# SCH12_AFE.net
KiCad netlist of a schematic drawn in Altium Designer
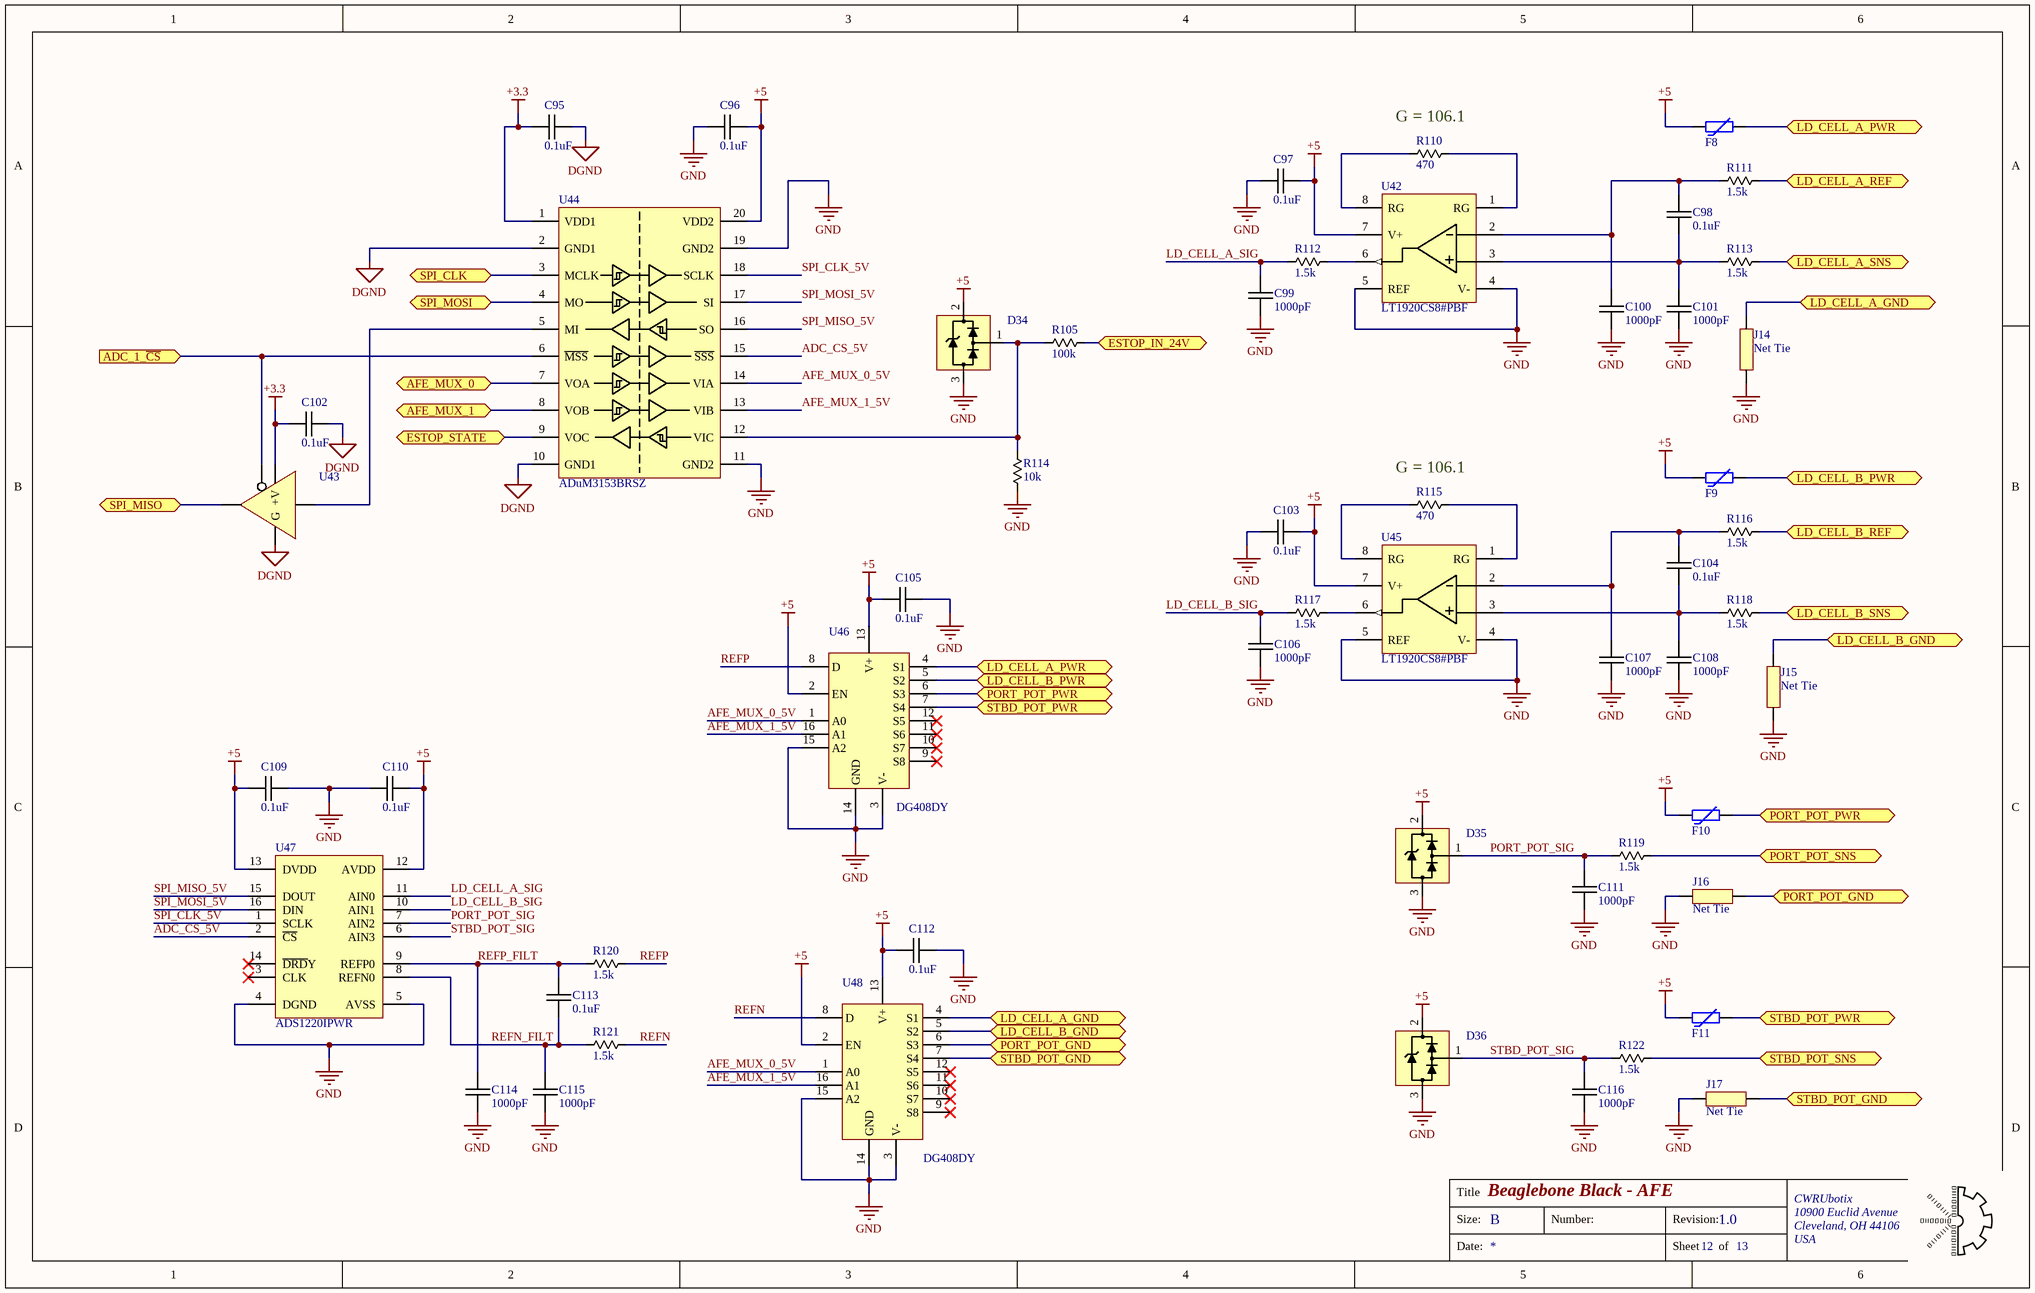
[diagram p0: SCH12_AFE.SchDoc]

(export (version "E")
  (design (tool "Eeschema 10.0.6"))
  (components
    (comp (ref "C95")
      (value "0.1uF")
      (footprint "chip_0603")
      (description "CAP, 0.1uF, ±10%, 16V, X7R, 0603")
      (fields (field (name "PART NUMBER") "CAP-00542") (field (name "TOLERANCE") "±10%"))
      (libsource (lib "Capacitors$") (part "CAP-00542"))
    )
    (comp (ref "C96")
      (value "0.1uF")
      (footprint "chip_0603")
      (description "CAP, 0.1uF, ±10%, 16V, X7R, 0603")
      (fields (field (name "PART NUMBER") "CAP-00542") (field (name "TOLERANCE") "±10%"))
      (libsource (lib "Capacitors$") (part "CAP-00542"))
    )
    (comp (ref "C97")
      (value "0.1uF")
      (footprint "chip_0603")
      (description "CAP, 0.1uF, ±10%, 16V, X7R, 0603")
      (fields (field (name "PART NUMBER") "CAP-00542") (field (name "TOLERANCE") "±10%"))
      (libsource (lib "Capacitors$") (part "CAP-00542"))
    )
    (comp (ref "C98")
      (value "0.1uF")
      (footprint "chip_0603")
      (description "CAP, 0.1uF, ±10%, 16V, X7R, 0603")
      (fields (field (name "PART NUMBER") "CAP-00542") (field (name "TOLERANCE") "±10%"))
      (libsource (lib "Capacitors$") (part "CAP-00542"))
    )
    (comp (ref "C99")
      (value "1000pF")
      (footprint "chip_0603")
      (description "CAP, 1000pF, ±1%, 50V, C0G, 0603")
      (fields (field (name "PART NUMBER") "CAP-00457") (field (name "TOLERANCE") "±1%"))
      (libsource (lib "Capacitors$") (part "CAP-00457"))
    )
    (comp (ref "C100")
      (value "1000pF")
      (footprint "chip_0603")
      (description "CAP, 1000pF, ±1%, 50V, C0G, 0603")
      (fields (field (name "PART NUMBER") "CAP-00457") (field (name "TOLERANCE") "±1%"))
      (libsource (lib "Capacitors$") (part "CAP-00457"))
    )
    (comp (ref "C101")
      (value "1000pF")
      (footprint "chip_0603")
      (description "CAP, 1000pF, ±1%, 50V, C0G, 0603")
      (fields (field (name "PART NUMBER") "CAP-00457") (field (name "TOLERANCE") "±1%"))
      (libsource (lib "Capacitors$") (part "CAP-00457"))
    )
    (comp (ref "C102")
      (value "0.1uF")
      (footprint "chip_0603")
      (description "CAP, 0.1uF, ±10%, 16V, X7R, 0603")
      (fields (field (name "PART NUMBER") "CAP-00542") (field (name "TOLERANCE") "±10%"))
      (libsource (lib "Capacitors$") (part "CAP-00542"))
    )
    (comp (ref "C103")
      (value "0.1uF")
      (footprint "chip_0603")
      (description "CAP, 0.1uF, ±10%, 16V, X7R, 0603")
      (fields (field (name "PART NUMBER") "CAP-00542") (field (name "TOLERANCE") "±10%"))
      (libsource (lib "Capacitors$") (part "CAP-00542"))
    )
    (comp (ref "C104")
      (value "0.1uF")
      (footprint "chip_0603")
      (description "CAP, 0.1uF, ±10%, 16V, X7R, 0603")
      (fields (field (name "PART NUMBER") "CAP-00542") (field (name "TOLERANCE") "±10%"))
      (libsource (lib "Capacitors$") (part "CAP-00542"))
    )
    (comp (ref "C105")
      (value "0.1uF")
      (footprint "chip_0603")
      (description "CAP, 0.1uF, ±10%, 16V, X7R, 0603")
      (fields (field (name "PART NUMBER") "CAP-00542") (field (name "TOLERANCE") "±10%"))
      (libsource (lib "Capacitors$") (part "CAP-00542"))
    )
    (comp (ref "C106")
      (value "1000pF")
      (footprint "chip_0603")
      (description "CAP, 1000pF, ±1%, 50V, C0G, 0603")
      (fields (field (name "PART NUMBER") "CAP-00457") (field (name "TOLERANCE") "±1%"))
      (libsource (lib "Capacitors$") (part "CAP-00457"))
    )
    (comp (ref "C107")
      (value "1000pF")
      (footprint "chip_0603")
      (description "CAP, 1000pF, ±1%, 50V, C0G, 0603")
      (fields (field (name "PART NUMBER") "CAP-00457") (field (name "TOLERANCE") "±1%"))
      (libsource (lib "Capacitors$") (part "CAP-00457"))
    )
    (comp (ref "C108")
      (value "1000pF")
      (footprint "chip_0603")
      (description "CAP, 1000pF, ±1%, 50V, C0G, 0603")
      (fields (field (name "PART NUMBER") "CAP-00457") (field (name "TOLERANCE") "±1%"))
      (libsource (lib "Capacitors$") (part "CAP-00457"))
    )
    (comp (ref "C109")
      (value "0.1uF")
      (footprint "chip_0603")
      (description "CAP, 0.1uF, ±10%, 16V, X7R, 0603")
      (fields (field (name "PART NUMBER") "CAP-00542") (field (name "TOLERANCE") "±10%"))
      (libsource (lib "Capacitors$") (part "CAP-00542"))
    )
    (comp (ref "C110")
      (value "0.1uF")
      (footprint "chip_0603")
      (description "CAP, 0.1uF, ±10%, 16V, X7R, 0603")
      (fields (field (name "PART NUMBER") "CAP-00542") (field (name "TOLERANCE") "±10%"))
      (libsource (lib "Capacitors$") (part "CAP-00542"))
    )
    (comp (ref "C111")
      (value "1000pF")
      (footprint "chip_0603")
      (description "CAP, 1000pF, ±1%, 50V, C0G, 0603")
      (fields (field (name "PART NUMBER") "CAP-00457") (field (name "TOLERANCE") "±1%"))
      (libsource (lib "Capacitors$") (part "CAP-00457"))
    )
    (comp (ref "C112")
      (value "0.1uF")
      (footprint "chip_0603")
      (description "CAP, 0.1uF, ±10%, 16V, X7R, 0603")
      (fields (field (name "PART NUMBER") "CAP-00542") (field (name "TOLERANCE") "±10%"))
      (libsource (lib "Capacitors$") (part "CAP-00542"))
    )
    (comp (ref "C113")
      (value "0.1uF")
      (footprint "chip_0603")
      (description "CAP, 0.1uF, ±10%, 16V, X7R, 0603")
      (fields (field (name "PART NUMBER") "CAP-00542") (field (name "TOLERANCE") "±10%"))
      (libsource (lib "Capacitors$") (part "CAP-00542"))
    )
    (comp (ref "C114")
      (value "1000pF")
      (footprint "chip_0603")
      (description "CAP, 1000pF, ±1%, 50V, C0G, 0603")
      (fields (field (name "PART NUMBER") "CAP-00457") (field (name "TOLERANCE") "±1%"))
      (libsource (lib "Capacitors$") (part "CAP-00457"))
    )
    (comp (ref "C115")
      (value "1000pF")
      (footprint "chip_0603")
      (description "CAP, 1000pF, ±1%, 50V, C0G, 0603")
      (fields (field (name "PART NUMBER") "CAP-00457") (field (name "TOLERANCE") "±1%"))
      (libsource (lib "Capacitors$") (part "CAP-00457"))
    )
    (comp (ref "C116")
      (value "1000pF")
      (footprint "chip_0603")
      (description "CAP, 1000pF, ±1%, 50V, C0G, 0603")
      (fields (field (name "PART NUMBER") "CAP-00457") (field (name "TOLERANCE") "±1%"))
      (libsource (lib "Capacitors$") (part "CAP-00457"))
    )
    (comp (ref "D34")
      (value "DLPT05")
      (footprint "sot-23-3")
      (description "TVS, Steering (Rail-Rail), 9.8V Clamping, 17A Peak Pulse, SOT-23")
      (fields (field (name "PART NUMBER") "DIO-00057") (field (name "MANUFACTURER") "Diodes Incorporated"))
      (libsource (lib "Diodes$") (part "DIO-00057"))
    )
    (comp (ref "D35")
      (value "DLPT05")
      (footprint "sot-23-3")
      (description "TVS, Steering (Rail-Rail), 9.8V Clamping, 17A Peak Pulse, SOT-23")
      (fields (field (name "PART NUMBER") "DIO-00057") (field (name "MANUFACTURER") "Diodes Incorporated"))
      (libsource (lib "Diodes$") (part "DIO-00057"))
    )
    (comp (ref "D36")
      (value "DLPT05")
      (footprint "sot-23-3")
      (description "TVS, Steering (Rail-Rail), 9.8V Clamping, 17A Peak Pulse, SOT-23")
      (fields (field (name "PART NUMBER") "DIO-00057") (field (name "MANUFACTURER") "Diodes Incorporated"))
      (libsource (lib "Diodes$") (part "DIO-00057"))
    )
    (comp (ref "F8")
      (value "PTC_0")
      (footprint "chip_1206")
      (description "PTC Resettable fuse, 6V, 500mA, 1206")
      (fields (field (name "PART NUMBER") "MISC-00008") (field (name "MANUFACTURER") "Eaton"))
      (libsource (lib "Misc$") (part "MISC-00008"))
    )
    (comp (ref "F9")
      (value "PTC_0")
      (footprint "chip_1206")
      (description "PTC Resettable fuse, 6V, 500mA, 1206")
      (fields (field (name "PART NUMBER") "MISC-00008") (field (name "MANUFACTURER") "Eaton"))
      (libsource (lib "Misc$") (part "MISC-00008"))
    )
    (comp (ref "F10")
      (value "PTC_0")
      (footprint "chip_1206")
      (description "PTC Resettable fuse, 6V, 500mA, 1206")
      (fields (field (name "PART NUMBER") "MISC-00008") (field (name "MANUFACTURER") "Eaton"))
      (libsource (lib "Misc$") (part "MISC-00008"))
    )
    (comp (ref "F11")
      (value "PTC_0")
      (footprint "chip_1206")
      (description "PTC Resettable fuse, 6V, 500mA, 1206")
      (fields (field (name "PART NUMBER") "MISC-00008") (field (name "MANUFACTURER") "Eaton"))
      (libsource (lib "Misc$") (part "MISC-00008"))
    )
    (comp (ref "J14")
      (value "Net Tie")
      (footprint "net_tie_0")
      (fields (field (name "PART NUMBER") "MISC-00039"))
      (libsource (lib "") (part "MISC-00039_1"))
    )
    (comp (ref "J15")
      (value "Net Tie")
      (footprint "net_tie_0")
      (fields (field (name "PART NUMBER") "MISC-00039"))
      (libsource (lib "") (part "MISC-00039_1"))
    )
    (comp (ref "J16")
      (value "Net Tie")
      (footprint "net_tie_0")
      (fields (field (name "PART NUMBER") "MISC-00039"))
      (libsource (lib "Misc$") (part "MISC-00039"))
    )
    (comp (ref "J17")
      (value "Net Tie")
      (footprint "net_tie_0")
      (fields (field (name "PART NUMBER") "MISC-00039"))
      (libsource (lib "Misc$") (part "MISC-00039"))
    )
    (comp (ref "R105")
      (value "100k")
      (footprint "chip_0603")
      (description "RES SMD 100K OHM 1% 1/4W 0603")
      (fields (field (name "PART NUMBER") "RES-00301") (field (name "TOLERANCE") "1%"))
      (libsource (lib "Resistors$") (part "RES-00301"))
    )
    (comp (ref "R110")
      (value "470")
      (footprint "chip_0805")
      (description "RES SMD 470 OHM 1% 1/8W 0805")
      (fields (field (name "PART NUMBER") "RES-00237") (field (name "TOLERANCE") "1%"))
      (libsource (lib "Resistors$") (part "RES-00237"))
    )
    (comp (ref "R111")
      (value "1.5k")
      (footprint "chip_0603")
      (description "RES SMD 1.5K OHM 1% 1/4W 0603")
      (fields (field (name "PART NUMBER") "RES-00284") (field (name "TOLERANCE") "1%"))
      (libsource (lib "Resistors$") (part "RES-00284"))
    )
    (comp (ref "R112")
      (value "1.5k")
      (footprint "chip_0603")
      (description "RES SMD 1.5K OHM 1% 1/4W 0603")
      (fields (field (name "PART NUMBER") "RES-00284") (field (name "TOLERANCE") "1%"))
      (libsource (lib "Resistors$") (part "RES-00284"))
    )
    (comp (ref "R113")
      (value "1.5k")
      (footprint "chip_0603")
      (description "RES SMD 1.5K OHM 1% 1/4W 0603")
      (fields (field (name "PART NUMBER") "RES-00284") (field (name "TOLERANCE") "1%"))
      (libsource (lib "Resistors$") (part "RES-00284"))
    )
    (comp (ref "R114")
      (value "10k")
      (footprint "chip_0603")
      (description "RES SMD 10K OHM 1% 1/4W 0603")
      (fields (field (name "PART NUMBER") "RES-00306") (field (name "TOLERANCE") "1%"))
      (libsource (lib "Resistors$") (part "RES-00306"))
    )
    (comp (ref "R115")
      (value "470")
      (footprint "chip_0805")
      (description "RES SMD 470 OHM 1% 1/8W 0805")
      (fields (field (name "PART NUMBER") "RES-00237") (field (name "TOLERANCE") "1%"))
      (libsource (lib "Resistors$") (part "RES-00237"))
    )
    (comp (ref "R116")
      (value "1.5k")
      (footprint "chip_0603")
      (description "RES SMD 1.5K OHM 1% 1/4W 0603")
      (fields (field (name "PART NUMBER") "RES-00284") (field (name "TOLERANCE") "1%"))
      (libsource (lib "Resistors$") (part "RES-00284"))
    )
    (comp (ref "R117")
      (value "1.5k")
      (footprint "chip_0603")
      (description "RES SMD 1.5K OHM 1% 1/4W 0603")
      (fields (field (name "PART NUMBER") "RES-00284") (field (name "TOLERANCE") "1%"))
      (libsource (lib "Resistors$") (part "RES-00284"))
    )
    (comp (ref "R118")
      (value "1.5k")
      (footprint "chip_0603")
      (description "RES SMD 1.5K OHM 1% 1/4W 0603")
      (fields (field (name "PART NUMBER") "RES-00284") (field (name "TOLERANCE") "1%"))
      (libsource (lib "Resistors$") (part "RES-00284"))
    )
    (comp (ref "R119")
      (value "1.5k")
      (footprint "chip_0603")
      (description "RES SMD 1.5K OHM 1% 1/4W 0603")
      (fields (field (name "PART NUMBER") "RES-00284") (field (name "TOLERANCE") "1%"))
      (libsource (lib "Resistors$") (part "RES-00284"))
    )
    (comp (ref "R120")
      (value "1.5k")
      (footprint "chip_0603")
      (description "RES SMD 1.5K OHM 1% 1/4W 0603")
      (fields (field (name "PART NUMBER") "RES-00284") (field (name "TOLERANCE") "1%"))
      (libsource (lib "Resistors$") (part "RES-00284"))
    )
    (comp (ref "R121")
      (value "1.5k")
      (footprint "chip_0603")
      (description "RES SMD 1.5K OHM 1% 1/4W 0603")
      (fields (field (name "PART NUMBER") "RES-00284") (field (name "TOLERANCE") "1%"))
      (libsource (lib "Resistors$") (part "RES-00284"))
    )
    (comp (ref "R122")
      (value "1.5k")
      (footprint "chip_0603")
      (description "RES SMD 1.5K OHM 1% 1/4W 0603")
      (fields (field (name "PART NUMBER") "RES-00284") (field (name "TOLERANCE") "1%"))
      (libsource (lib "Resistors$") (part "RES-00284"))
    )
    (comp (ref "U42")
      (value "LT1920CS8#PBF")
      (footprint "SO-8_1")
      (description "IC, Instrumentation Amp, Single, 4.6 ~ 36V supply, SOIC-8")
      (fields (field (name "PART NUMBER") "ANLG-00071") (field (name "MANUFACTURER") "Linear Technology"))
      (libsource (lib "Analog$") (part "ANLG-00071"))
    )
    (comp (ref "U43")
      (value "SN74AHCT1G125")
      (footprint "sot-23-5")
      (description "Tri-State Buffer, Single, 2-5.5V, SOT-23-5, SN74AHC1G125")
      (fields (field (name "PART NUMBER") "LOGIC-00027") (field (name "MANUFACTURER") "TI"))
      (libsource (lib "Logic$") (part "LOGIC-00027"))
    )
    (comp (ref "U44")
      (value "ADuM3153BRSZ")
      (footprint "tssop-20_1")
      (description "Digital Isolator, SPI-bus optomized, ADuM3151")
      (fields (field (name "PART NUMBER") "IFACE-00029") (field (name "MANUFACTURER") "Analog Devices"))
      (libsource (lib "Interfaces$") (part "IFACE-00029"))
    )
    (comp (ref "U45")
      (value "LT1920CS8#PBF")
      (footprint "SO-8_1")
      (description "IC, Instrumentation Amp, Single, 4.6 ~ 36V supply, SOIC-8")
      (fields (field (name "PART NUMBER") "ANLG-00071") (field (name "MANUFACTURER") "Linear Technology"))
      (libsource (lib "Analog$") (part "ANLG-00071"))
    )
    (comp (ref "U46")
      (value "DG408DY")
      (footprint "SO-16_1")
      (description "Analog Mux, 8:1, 5 ~ 36V, SOIC-16")
      (fields (field (name "PART NUMBER") "ANLG-00072") (field (name "MANUFACTURER") "Vishay"))
      (libsource (lib "Analog$") (part "ANLG-00072"))
    )
    (comp (ref "U47")
      (value "ADS1220IPWR")
      (footprint "TSSOP-16_0_1")
      (description "IC, ADC 24-bit 4-Channel MUX-PGA, Sigma-Delta, 2k SPS, 16-TSSOP")
      (fields (field (name "PART NUMBER") "ANLG-00073") (field (name "MANUFACTURER") "TI"))
      (libsource (lib "Analog$") (part "ANLG-00073"))
    )
    (comp (ref "U48")
      (value "DG408DY")
      (footprint "SO-16_1")
      (description "Analog Mux, 8:1, 5 ~ 36V, SOIC-16")
      (fields (field (name "PART NUMBER") "ANLG-00072") (field (name "MANUFACTURER") "Vishay"))
      (libsource (lib "Analog$") (part "ANLG-00072"))
    )
  )
  (nets
    (net (code "1") (name "+3.3") (class "Default")
      (node (ref "C102") (pin "2") (pinfunction "2_2") (pintype "passive"))
      (node (ref "C95") (pin "2") (pinfunction "2_2") (pintype "passive"))
      (node (ref "U43") (pin "5") (pinfunction "+V_5") (pintype "passive"))
      (node (ref "U44") (pin "1") (pinfunction "VDD1_1") (pintype "passive"))
    )
    (net (code "2") (name "+5") (class "Default")
      (node (ref "C103") (pin "1") (pinfunction "1_1") (pintype "passive"))
      (node (ref "C105") (pin "2") (pinfunction "2_2") (pintype "passive"))
      (node (ref "C109") (pin "2") (pinfunction "2_2") (pintype "passive"))
      (node (ref "C110") (pin "1") (pinfunction "1_1") (pintype "passive"))
      (node (ref "C112") (pin "2") (pinfunction "2_2") (pintype "passive"))
      (node (ref "C96") (pin "1") (pinfunction "1_1") (pintype "passive"))
      (node (ref "C97") (pin "1") (pinfunction "1_1") (pintype "passive"))
      (node (ref "D34") (pin "2") (pinfunction "VCC_2") (pintype "passive"))
      (node (ref "D35") (pin "2") (pinfunction "VCC_2") (pintype "passive"))
      (node (ref "D36") (pin "2") (pinfunction "VCC_2") (pintype "passive"))
      (node (ref "F10") (pin "1") (pinfunction "1_1") (pintype "passive"))
      (node (ref "F11") (pin "1") (pinfunction "1_1") (pintype "passive"))
      (node (ref "F8") (pin "1") (pinfunction "1_1") (pintype "passive"))
      (node (ref "F9") (pin "1") (pinfunction "1_1") (pintype "passive"))
      (node (ref "U42") (pin "7") (pinfunction "V+_7") (pintype "power_in"))
      (node (ref "U44") (pin "20") (pinfunction "VDD2_20") (pintype "passive"))
      (node (ref "U45") (pin "7") (pinfunction "V+_7") (pintype "power_in"))
      (node (ref "U46") (pin "13") (pinfunction "V+_13") (pintype "passive"))
      (node (ref "U46") (pin "2") (pinfunction "EN_2") (pintype "passive"))
      (node (ref "U47") (pin "12") (pinfunction "AVDD_12") (pintype "passive"))
      (node (ref "U47") (pin "13") (pinfunction "DVDD_13") (pintype "passive"))
      (node (ref "U48") (pin "13") (pinfunction "V+_13") (pintype "passive"))
      (node (ref "U48") (pin "2") (pinfunction "EN_2") (pintype "passive"))
    )
    (net (code "3") (name "/ADC_1_~{CS}") (class "Default")
      (node (ref "U43") (pin "1") (pinfunction "~{OE}_1") (pintype "passive"))
      (node (ref "U44") (pin "6") (pinfunction "~{MSS}_6") (pintype "passive"))
    )
    (net (code "4") (name "/ADC_CS_5V") (class "Default")
      (node (ref "U44") (pin "15") (pinfunction "~{SSS}_15") (pintype "passive"))
      (node (ref "U47") (pin "2") (pinfunction "~{CS}_2") (pintype "passive"))
    )
    (net (code "5") (name "/AFE_MUX_0") (class "Default")
      (node (ref "U44") (pin "7") (pinfunction "VOA_7") (pintype "passive"))
    )
    (net (code "6") (name "/AFE_MUX_0_5V") (class "Default")
      (node (ref "U44") (pin "14") (pinfunction "VIA_14") (pintype "passive"))
      (node (ref "U46") (pin "1") (pinfunction "A0_1") (pintype "passive"))
      (node (ref "U48") (pin "1") (pinfunction "A0_1") (pintype "passive"))
    )
    (net (code "7") (name "/AFE_MUX_1") (class "Default")
      (node (ref "U44") (pin "8") (pinfunction "VOB_8") (pintype "passive"))
    )
    (net (code "8") (name "/AFE_MUX_1_5V") (class "Default")
      (node (ref "U44") (pin "13") (pinfunction "VIB_13") (pintype "passive"))
      (node (ref "U46") (pin "16") (pinfunction "A1_16") (pintype "passive"))
      (node (ref "U48") (pin "16") (pinfunction "A1_16") (pintype "passive"))
    )
    (net (code "9") (name "/ESTOP_IN_24V") (class "Default")
      (node (ref "R105") (pin "2") (pinfunction "2_2") (pintype "passive"))
    )
    (net (code "10") (name "/ESTOP_STATE") (class "Default")
      (node (ref "U44") (pin "9") (pinfunction "VOC_9") (pintype "passive"))
    )
    (net (code "11") (name "/LD_CELL_A_GND") (class "Default")
      (node (ref "J14") (pin "2") (pinfunction "NET2_2") (pintype "power_in"))
      (node (ref "U48") (pin "4") (pinfunction "S1_4") (pintype "passive"))
    )
    (net (code "12") (name "/LD_CELL_A_PWR") (class "Default")
      (node (ref "F8") (pin "2") (pinfunction "2_2") (pintype "passive"))
      (node (ref "U46") (pin "4") (pinfunction "S1_4") (pintype "passive"))
    )
    (net (code "13") (name "/LD_CELL_A_REF") (class "Default")
      (node (ref "R111") (pin "2") (pinfunction "2_2") (pintype "passive"))
    )
    (net (code "14") (name "/LD_CELL_A_SIG") (class "Default")
      (node (ref "C99") (pin "1") (pinfunction "1_1") (pintype "passive"))
      (node (ref "R112") (pin "1") (pinfunction "1_1") (pintype "passive"))
      (node (ref "U47") (pin "11") (pinfunction "AIN0_11") (pintype "passive"))
    )
    (net (code "15") (name "/LD_CELL_A_SNS") (class "Default")
      (node (ref "R113") (pin "2") (pinfunction "2_2") (pintype "passive"))
    )
    (net (code "16") (name "/LD_CELL_B_GND") (class "Default")
      (node (ref "J15") (pin "2") (pinfunction "NET2_2") (pintype "power_in"))
      (node (ref "U48") (pin "5") (pinfunction "S2_5") (pintype "passive"))
    )
    (net (code "17") (name "/LD_CELL_B_PWR") (class "Default")
      (node (ref "F9") (pin "2") (pinfunction "2_2") (pintype "passive"))
      (node (ref "U46") (pin "5") (pinfunction "S2_5") (pintype "passive"))
    )
    (net (code "18") (name "/LD_CELL_B_REF") (class "Default")
      (node (ref "R116") (pin "2") (pinfunction "2_2") (pintype "passive"))
    )
    (net (code "19") (name "/LD_CELL_B_SIG") (class "Default")
      (node (ref "C106") (pin "1") (pinfunction "1_1") (pintype "passive"))
      (node (ref "R117") (pin "1") (pinfunction "1_1") (pintype "passive"))
      (node (ref "U47") (pin "10") (pinfunction "AIN1_10") (pintype "passive"))
    )
    (net (code "20") (name "/LD_CELL_B_SNS") (class "Default")
      (node (ref "R118") (pin "2") (pinfunction "2_2") (pintype "passive"))
    )
    (net (code "21") (name "/PORT_POT_GND") (class "Default")
      (node (ref "J16") (pin "2") (pinfunction "NET2_2") (pintype "power_in"))
      (node (ref "U48") (pin "6") (pinfunction "S3_6") (pintype "passive"))
    )
    (net (code "22") (name "/PORT_POT_PWR") (class "Default")
      (node (ref "F10") (pin "2") (pinfunction "2_2") (pintype "passive"))
      (node (ref "U46") (pin "6") (pinfunction "S3_6") (pintype "passive"))
    )
    (net (code "23") (name "/PORT_POT_SIG") (class "Default")
      (node (ref "C111") (pin "1") (pinfunction "1_1") (pintype "passive"))
      (node (ref "D35") (pin "1") (pinfunction "LINE_1") (pintype "passive"))
      (node (ref "R119") (pin "1") (pinfunction "1_1") (pintype "passive"))
      (node (ref "U47") (pin "7") (pinfunction "AIN2_7") (pintype "passive"))
    )
    (net (code "24") (name "/PORT_POT_SNS") (class "Default")
      (node (ref "R119") (pin "2") (pinfunction "2_2") (pintype "passive"))
    )
    (net (code "25") (name "/REFN") (class "Default")
      (node (ref "R121") (pin "2") (pinfunction "2_2") (pintype "passive"))
      (node (ref "U48") (pin "8") (pinfunction "D_8") (pintype "passive"))
    )
    (net (code "26") (name "/REFN_FILT") (class "Default")
      (node (ref "C113") (pin "2") (pinfunction "2_2") (pintype "passive"))
      (node (ref "C115") (pin "1") (pinfunction "1_1") (pintype "passive"))
      (node (ref "R121") (pin "1") (pinfunction "1_1") (pintype "passive"))
      (node (ref "U47") (pin "8") (pinfunction "REFN0_8") (pintype "passive"))
    )
    (net (code "27") (name "/REFP") (class "Default")
      (node (ref "R120") (pin "2") (pinfunction "2_2") (pintype "passive"))
      (node (ref "U46") (pin "8") (pinfunction "D_8") (pintype "passive"))
    )
    (net (code "28") (name "/REFP_FILT") (class "Default")
      (node (ref "C113") (pin "1") (pinfunction "1_1") (pintype "passive"))
      (node (ref "C114") (pin "1") (pinfunction "1_1") (pintype "passive"))
      (node (ref "R120") (pin "1") (pinfunction "1_1") (pintype "passive"))
      (node (ref "U47") (pin "9") (pinfunction "REFP0_9") (pintype "passive"))
    )
    (net (code "29") (name "/SPI_CLK") (class "Default")
      (node (ref "U44") (pin "3") (pinfunction "MCLK_3") (pintype "passive"))
    )
    (net (code "30") (name "/SPI_CLK_5V") (class "Default")
      (node (ref "U44") (pin "18") (pinfunction "SCLK_18") (pintype "passive"))
      (node (ref "U47") (pin "1") (pinfunction "SCLK_1") (pintype "passive"))
    )
    (net (code "31") (name "/SPI_MISO") (class "Default")
      (node (ref "U43") (pin "4") (pinfunction "Y_4") (pintype "passive"))
    )
    (net (code "32") (name "/SPI_MISO_5V") (class "Default")
      (node (ref "U44") (pin "16") (pinfunction "SO_16") (pintype "passive"))
      (node (ref "U47") (pin "15") (pinfunction "DOUT_15") (pintype "passive"))
    )
    (net (code "33") (name "/SPI_MOSI") (class "Default")
      (node (ref "U44") (pin "4") (pinfunction "MO_4") (pintype "passive"))
    )
    (net (code "34") (name "/SPI_MOSI_5V") (class "Default")
      (node (ref "U44") (pin "17") (pinfunction "SI_17") (pintype "passive"))
      (node (ref "U47") (pin "16") (pinfunction "DIN_16") (pintype "passive"))
    )
    (net (code "35") (name "/STBD_POT_GND") (class "Default")
      (node (ref "J17") (pin "2") (pinfunction "NET2_2") (pintype "power_in"))
      (node (ref "U48") (pin "7") (pinfunction "S4_7") (pintype "passive"))
    )
    (net (code "36") (name "/STBD_POT_PWR") (class "Default")
      (node (ref "F11") (pin "2") (pinfunction "2_2") (pintype "passive"))
      (node (ref "U46") (pin "7") (pinfunction "S4_7") (pintype "passive"))
    )
    (net (code "37") (name "/STBD_POT_SIG") (class "Default")
      (node (ref "C116") (pin "1") (pinfunction "1_1") (pintype "passive"))
      (node (ref "D36") (pin "1") (pinfunction "LINE_1") (pintype "passive"))
      (node (ref "R122") (pin "1") (pinfunction "1_1") (pintype "passive"))
      (node (ref "U47") (pin "6") (pinfunction "AIN3_6") (pintype "passive"))
    )
    (net (code "38") (name "/STBD_POT_SNS") (class "Default")
      (node (ref "R122") (pin "2") (pinfunction "2_2") (pintype "passive"))
    )
    (net (code "39") (name "DGND") (class "Default")
      (node (ref "C102") (pin "1") (pinfunction "1_1") (pintype "passive"))
      (node (ref "C95") (pin "1") (pinfunction "1_1") (pintype "passive"))
      (node (ref "U43") (pin "3") (pinfunction "G_3") (pintype "passive"))
      (node (ref "U44") (pin "10") (pinfunction "GND1_10") (pintype "passive"))
      (node (ref "U44") (pin "2") (pinfunction "GND1_2") (pintype "passive"))
    )
    (net (code "40") (name "GND") (class "Default")
      (node (ref "C100") (pin "2") (pinfunction "2_2") (pintype "passive"))
      (node (ref "C101") (pin "2") (pinfunction "2_2") (pintype "passive"))
      (node (ref "C103") (pin "2") (pinfunction "2_2") (pintype "passive"))
      (node (ref "C105") (pin "1") (pinfunction "1_1") (pintype "passive"))
      (node (ref "C106") (pin "2") (pinfunction "2_2") (pintype "passive"))
      (node (ref "C107") (pin "2") (pinfunction "2_2") (pintype "passive"))
      (node (ref "C108") (pin "2") (pinfunction "2_2") (pintype "passive"))
      (node (ref "C109") (pin "1") (pinfunction "1_1") (pintype "passive"))
      (node (ref "C110") (pin "2") (pinfunction "2_2") (pintype "passive"))
      (node (ref "C111") (pin "2") (pinfunction "2_2") (pintype "passive"))
      (node (ref "C112") (pin "1") (pinfunction "1_1") (pintype "passive"))
      (node (ref "C114") (pin "2") (pinfunction "2_2") (pintype "passive"))
      (node (ref "C115") (pin "2") (pinfunction "2_2") (pintype "passive"))
      (node (ref "C116") (pin "2") (pinfunction "2_2") (pintype "passive"))
      (node (ref "C96") (pin "2") (pinfunction "2_2") (pintype "passive"))
      (node (ref "C97") (pin "2") (pinfunction "2_2") (pintype "passive"))
      (node (ref "C99") (pin "2") (pinfunction "2_2") (pintype "passive"))
      (node (ref "D34") (pin "3") (pinfunction "GND_3") (pintype "passive"))
      (node (ref "D35") (pin "3") (pinfunction "GND_3") (pintype "passive"))
      (node (ref "D36") (pin "3") (pinfunction "GND_3") (pintype "passive"))
      (node (ref "J14") (pin "1") (pinfunction "NET1_1") (pintype "power_in"))
      (node (ref "J15") (pin "1") (pinfunction "NET1_1") (pintype "power_in"))
      (node (ref "J16") (pin "1") (pinfunction "NET1_1") (pintype "power_in"))
      (node (ref "J17") (pin "1") (pinfunction "NET1_1") (pintype "power_in"))
      (node (ref "R114") (pin "2") (pinfunction "2_2") (pintype "passive"))
      (node (ref "U42") (pin "4") (pinfunction "V-_4") (pintype "power_in"))
      (node (ref "U42") (pin "5") (pinfunction "REF_5") (pintype "passive"))
      (node (ref "U44") (pin "11") (pinfunction "GND2_11") (pintype "passive"))
      (node (ref "U44") (pin "19") (pinfunction "GND2_19") (pintype "passive"))
      (node (ref "U45") (pin "4") (pinfunction "V-_4") (pintype "power_in"))
      (node (ref "U45") (pin "5") (pinfunction "REF_5") (pintype "passive"))
      (node (ref "U46") (pin "14") (pinfunction "GND_14") (pintype "passive"))
      (node (ref "U46") (pin "15") (pinfunction "A2_15") (pintype "passive"))
      (node (ref "U46") (pin "3") (pinfunction "V-_3") (pintype "passive"))
      (node (ref "U47") (pin "4") (pinfunction "DGND_4") (pintype "passive"))
      (node (ref "U47") (pin "5") (pinfunction "AVSS_5") (pintype "passive"))
      (node (ref "U48") (pin "14") (pinfunction "GND_14") (pintype "passive"))
      (node (ref "U48") (pin "15") (pinfunction "A2_15") (pintype "passive"))
      (node (ref "U48") (pin "3") (pinfunction "V-_3") (pintype "passive"))
    )
    (net (code "41") (name "Net-(D34-LINE)") (class "Default")
      (node (ref "D34") (pin "1") (pinfunction "LINE_1") (pintype "passive"))
      (node (ref "R105") (pin "1") (pinfunction "1_1") (pintype "passive"))
      (node (ref "R114") (pin "1") (pinfunction "1_1") (pintype "passive"))
      (node (ref "U44") (pin "12") (pinfunction "VIC_12") (pintype "passive"))
    )
    (net (code "42") (name "Net-(R110-Pad1)") (class "Default")
      (node (ref "R110") (pin "1") (pinfunction "1_1") (pintype "passive"))
      (node (ref "U42") (pin "8") (pinfunction "RG_8") (pintype "passive"))
    )
    (net (code "43") (name "Net-(R110-Pad2)") (class "Default")
      (node (ref "R110") (pin "2") (pinfunction "2_2") (pintype "passive"))
      (node (ref "U42") (pin "1") (pinfunction "RG_1") (pintype "passive"))
    )
    (net (code "44") (name "Net-(R115-Pad1)") (class "Default")
      (node (ref "R115") (pin "1") (pinfunction "1_1") (pintype "passive"))
      (node (ref "U45") (pin "8") (pinfunction "RG_8") (pintype "passive"))
    )
    (net (code "45") (name "Net-(R115-Pad2)") (class "Default")
      (node (ref "R115") (pin "2") (pinfunction "2_2") (pintype "passive"))
      (node (ref "U45") (pin "1") (pinfunction "RG_1") (pintype "passive"))
    )
    (net (code "46") (name "Net-(U42-+IN)") (class "Default")
      (node (ref "C101") (pin "1") (pinfunction "1_1") (pintype "passive"))
      (node (ref "C98") (pin "2") (pinfunction "2_2") (pintype "passive"))
      (node (ref "R113") (pin "1") (pinfunction "1_1") (pintype "passive"))
      (node (ref "U42") (pin "3") (pinfunction "+IN_3") (pintype "passive"))
    )
    (net (code "47") (name "Net-(U42--IN)") (class "Default")
      (node (ref "C100") (pin "1") (pinfunction "1_1") (pintype "passive"))
      (node (ref "C98") (pin "1") (pinfunction "1_1") (pintype "passive"))
      (node (ref "R111") (pin "1") (pinfunction "1_1") (pintype "passive"))
      (node (ref "U42") (pin "2") (pinfunction "-IN_2") (pintype "passive"))
    )
    (net (code "48") (name "Net-(U42-OUT)") (class "Default")
      (node (ref "R112") (pin "2") (pinfunction "2_2") (pintype "passive"))
      (node (ref "U42") (pin "6") (pinfunction "OUT_6") (pintype "output"))
    )
    (net (code "49") (name "Net-(U43-A)") (class "Default")
      (node (ref "U43") (pin "2") (pinfunction "A_2") (pintype "passive"))
      (node (ref "U44") (pin "5") (pinfunction "MI_5") (pintype "passive"))
    )
    (net (code "50") (name "Net-(U45-+IN)") (class "Default")
      (node (ref "C104") (pin "2") (pinfunction "2_2") (pintype "passive"))
      (node (ref "C108") (pin "1") (pinfunction "1_1") (pintype "passive"))
      (node (ref "R118") (pin "1") (pinfunction "1_1") (pintype "passive"))
      (node (ref "U45") (pin "3") (pinfunction "+IN_3") (pintype "passive"))
    )
    (net (code "51") (name "Net-(U45--IN)") (class "Default")
      (node (ref "C104") (pin "1") (pinfunction "1_1") (pintype "passive"))
      (node (ref "C107") (pin "1") (pinfunction "1_1") (pintype "passive"))
      (node (ref "R116") (pin "1") (pinfunction "1_1") (pintype "passive"))
      (node (ref "U45") (pin "2") (pinfunction "-IN_2") (pintype "passive"))
    )
    (net (code "52") (name "Net-(U45-OUT)") (class "Default")
      (node (ref "R117") (pin "2") (pinfunction "2_2") (pintype "passive"))
      (node (ref "U45") (pin "6") (pinfunction "OUT_6") (pintype "output"))
    )
    (net (code "53") (name "unconnected-(U46-S5-Pad12)") (class "Default")
      (node (ref "U46") (pin "12") (pinfunction "S5_12") (pintype "passive+no_connect"))
    )
    (net (code "54") (name "unconnected-(U46-S6-Pad11)") (class "Default")
      (node (ref "U46") (pin "11") (pinfunction "S6_11") (pintype "passive+no_connect"))
    )
    (net (code "55") (name "unconnected-(U46-S7-Pad10)") (class "Default")
      (node (ref "U46") (pin "10") (pinfunction "S7_10") (pintype "passive+no_connect"))
    )
    (net (code "56") (name "unconnected-(U46-S8-Pad9)") (class "Default")
      (node (ref "U46") (pin "9") (pinfunction "S8_9") (pintype "passive+no_connect"))
    )
    (net (code "57") (name "unconnected-(U47-CLK-Pad3)") (class "Default")
      (node (ref "U47") (pin "3") (pinfunction "CLK_3") (pintype "passive+no_connect"))
    )
    (net (code "58") (name "unconnected-(U47-~{DRD}Y-Pad14)") (class "Default")
      (node (ref "U47") (pin "14") (pinfunction "~{DRD}Y_14") (pintype "passive+no_connect"))
    )
    (net (code "59") (name "unconnected-(U48-S5-Pad12)") (class "Default")
      (node (ref "U48") (pin "12") (pinfunction "S5_12") (pintype "passive+no_connect"))
    )
    (net (code "60") (name "unconnected-(U48-S6-Pad11)") (class "Default")
      (node (ref "U48") (pin "11") (pinfunction "S6_11") (pintype "passive+no_connect"))
    )
    (net (code "61") (name "unconnected-(U48-S7-Pad10)") (class "Default")
      (node (ref "U48") (pin "10") (pinfunction "S7_10") (pintype "passive+no_connect"))
    )
    (net (code "62") (name "unconnected-(U48-S8-Pad9)") (class "Default")
      (node (ref "U48") (pin "9") (pinfunction "S8_9") (pintype "passive+no_connect"))
    )
  )
)
